# opentx.net
KiCad netlist of a schematic drawn in EAGLE
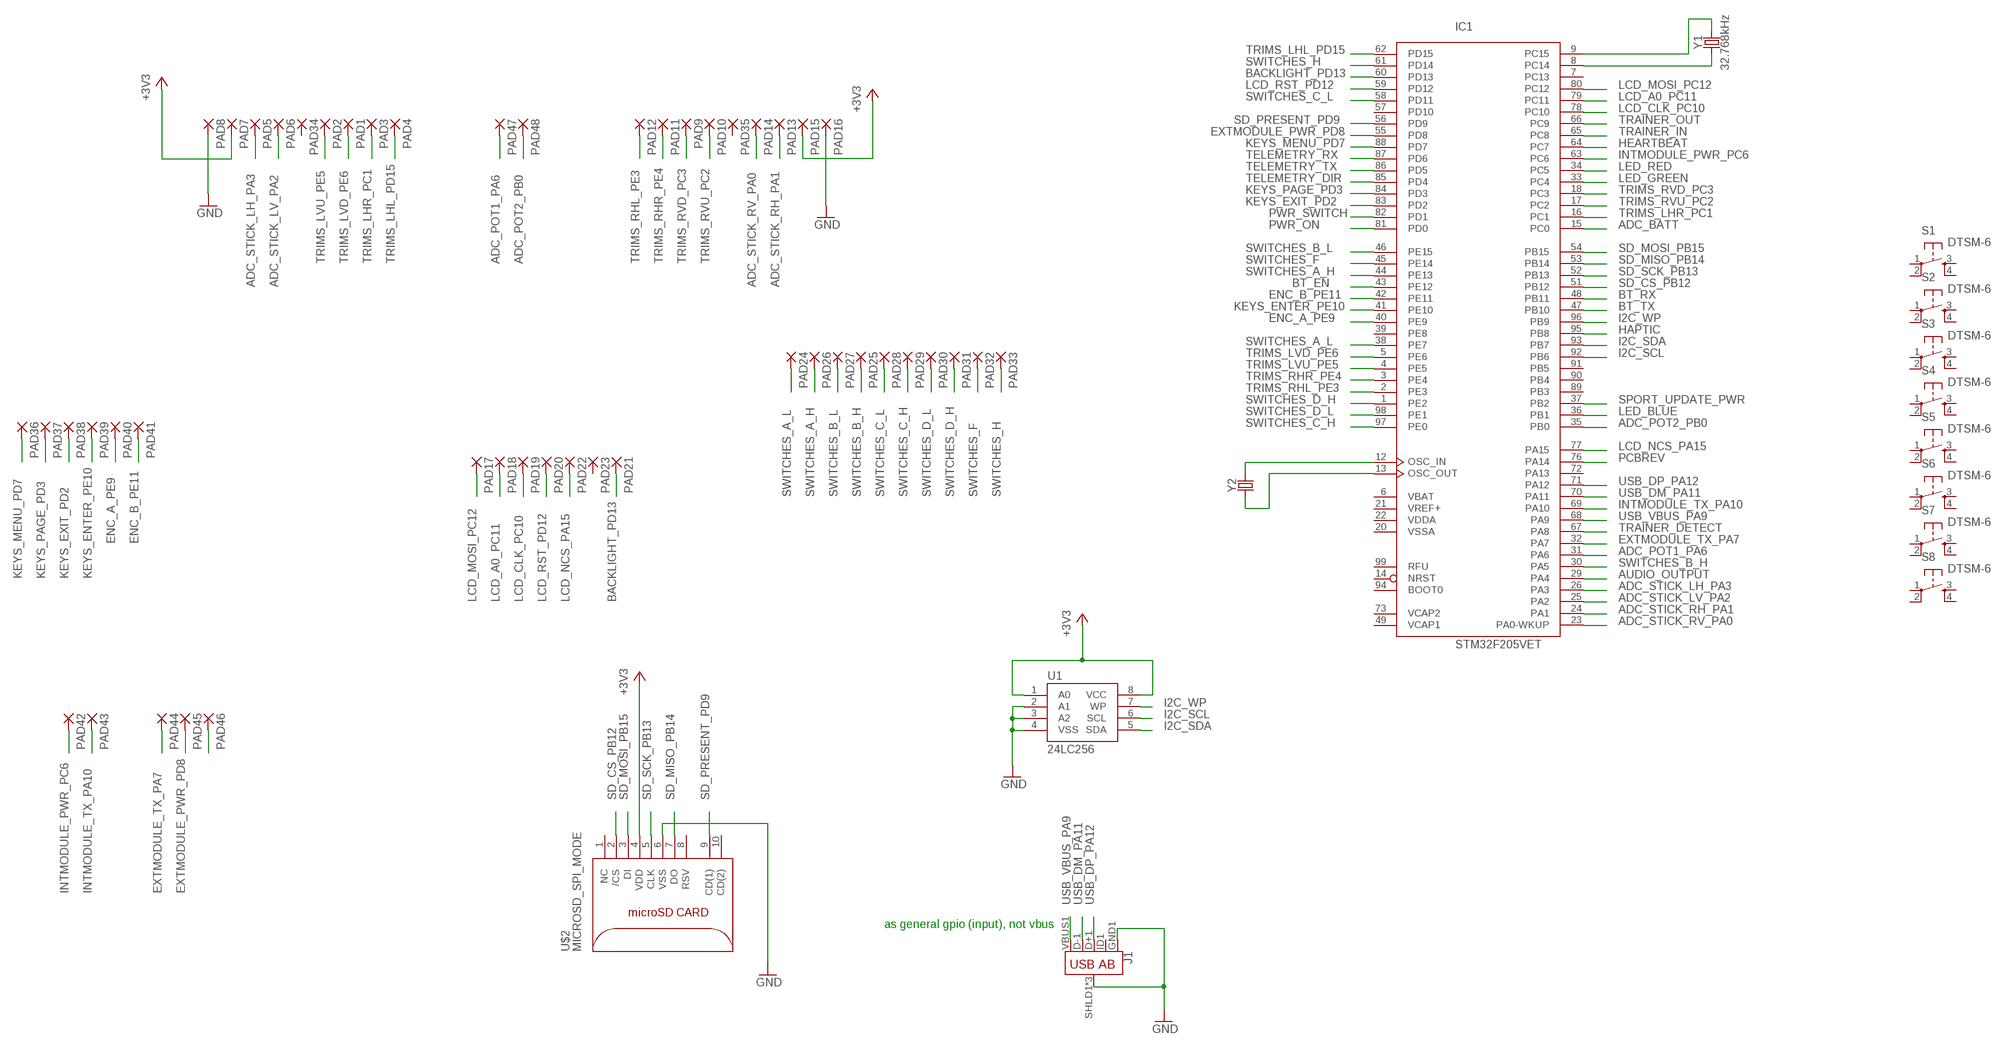
[diagram p0: schematic, sheet 1]

(export (version "E")
  (design (tool "Eeschema 10.0.6"))
  (components
    (comp (ref "IC1")
      (value "STM32F205VET")
      (footprint "eagle-import:LQFP100")
      (libsource (lib "eagle-import") (part "STM32F205VTE"))
    )
    (comp (ref "J1")
      (value "USB_AB_SMT")
      (footprint "eagle-import:USB-AB-MICRO-SMD")
      (libsource (lib "eagle-import") (part "USB_AB_SMT"))
    )
    (comp (ref "PAD1")
      (value "SMD2")
      (footprint "eagle-import:SMD1,27-2,54")
      (libsource (lib "eagle-import") (part "SMD2"))
    )
    (comp (ref "PAD2")
      (value "SMD2")
      (footprint "eagle-import:SMD1,27-2,54")
      (libsource (lib "eagle-import") (part "SMD2"))
    )
    (comp (ref "PAD3")
      (value "SMD2")
      (footprint "eagle-import:SMD1,27-2,54")
      (libsource (lib "eagle-import") (part "SMD2"))
    )
    (comp (ref "PAD4")
      (value "SMD2")
      (footprint "eagle-import:SMD1,27-2,54")
      (libsource (lib "eagle-import") (part "SMD2"))
    )
    (comp (ref "PAD5")
      (value "SMD2")
      (footprint "eagle-import:SMD1,27-2,54")
      (libsource (lib "eagle-import") (part "SMD2"))
    )
    (comp (ref "PAD6")
      (value "SMD2")
      (footprint "eagle-import:SMD1,27-2,54")
      (libsource (lib "eagle-import") (part "SMD2"))
    )
    (comp (ref "PAD7")
      (value "SMD2")
      (footprint "eagle-import:SMD1,27-2,54")
      (libsource (lib "eagle-import") (part "SMD2"))
    )
    (comp (ref "PAD8")
      (value "SMD2")
      (footprint "eagle-import:SMD1,27-2,54")
      (libsource (lib "eagle-import") (part "SMD2"))
    )
    (comp (ref "PAD9")
      (value "SMD2")
      (footprint "eagle-import:SMD1,27-2,54")
      (libsource (lib "eagle-import") (part "SMD2"))
    )
    (comp (ref "PAD10")
      (value "SMD2")
      (footprint "eagle-import:SMD1,27-2,54")
      (libsource (lib "eagle-import") (part "SMD2"))
    )
    (comp (ref "PAD11")
      (value "SMD2")
      (footprint "eagle-import:SMD1,27-2,54")
      (libsource (lib "eagle-import") (part "SMD2"))
    )
    (comp (ref "PAD12")
      (value "SMD2")
      (footprint "eagle-import:SMD1,27-2,54")
      (libsource (lib "eagle-import") (part "SMD2"))
    )
    (comp (ref "PAD13")
      (value "SMD2")
      (footprint "eagle-import:SMD1,27-2,54")
      (fields (field (name "SPICEPREFIX") "X"))
      (libsource (lib "eagle-import") (part "SMD2"))
    )
    (comp (ref "PAD14")
      (value "SMD2")
      (footprint "eagle-import:SMD1,27-2,54")
      (libsource (lib "eagle-import") (part "SMD2"))
    )
    (comp (ref "PAD15")
      (value "SMD2")
      (footprint "eagle-import:SMD1,27-2,54")
      (libsource (lib "eagle-import") (part "SMD2"))
    )
    (comp (ref "PAD16")
      (value "SMD2")
      (footprint "eagle-import:SMD1,27-2,54")
      (libsource (lib "eagle-import") (part "SMD2"))
    )
    (comp (ref "PAD17")
      (value "SMD2")
      (footprint "eagle-import:SMD1,27-2,54")
      (libsource (lib "eagle-import") (part "SMD2"))
    )
    (comp (ref "PAD18")
      (value "SMD2")
      (footprint "eagle-import:SMD1,27-2,54")
      (libsource (lib "eagle-import") (part "SMD2"))
    )
    (comp (ref "PAD19")
      (value "SMD2")
      (footprint "eagle-import:SMD1,27-2,54")
      (libsource (lib "eagle-import") (part "SMD2"))
    )
    (comp (ref "PAD20")
      (value "SMD2")
      (footprint "eagle-import:SMD1,27-2,54")
      (libsource (lib "eagle-import") (part "SMD2"))
    )
    (comp (ref "PAD21")
      (value "SMD2")
      (footprint "eagle-import:SMD1,27-2,54")
      (libsource (lib "eagle-import") (part "SMD2"))
    )
    (comp (ref "PAD22")
      (value "SMD2")
      (footprint "eagle-import:SMD1,27-2,54")
      (libsource (lib "eagle-import") (part "SMD2"))
    )
    (comp (ref "PAD23")
      (value "SMD2")
      (footprint "eagle-import:SMD1,27-2,54")
      (libsource (lib "eagle-import") (part "SMD2"))
    )
    (comp (ref "PAD24")
      (value "SMD2")
      (footprint "eagle-import:SMD1,27-2,54")
      (libsource (lib "eagle-import") (part "SMD2"))
    )
    (comp (ref "PAD25")
      (value "SMD2")
      (footprint "eagle-import:SMD1,27-2,54")
      (libsource (lib "eagle-import") (part "SMD2"))
    )
    (comp (ref "PAD26")
      (value "SMD2")
      (footprint "eagle-import:SMD1,27-2,54")
      (libsource (lib "eagle-import") (part "SMD2"))
    )
    (comp (ref "PAD27")
      (value "SMD2")
      (footprint "eagle-import:SMD1,27-2,54")
      (libsource (lib "eagle-import") (part "SMD2"))
    )
    (comp (ref "PAD28")
      (value "SMD2")
      (footprint "eagle-import:SMD1,27-2,54")
      (libsource (lib "eagle-import") (part "SMD2"))
    )
    (comp (ref "PAD29")
      (value "SMD2")
      (footprint "eagle-import:SMD1,27-2,54")
      (libsource (lib "eagle-import") (part "SMD2"))
    )
    (comp (ref "PAD30")
      (value "SMD2")
      (footprint "eagle-import:SMD1,27-2,54")
      (libsource (lib "eagle-import") (part "SMD2"))
    )
    (comp (ref "PAD31")
      (value "SMD2")
      (footprint "eagle-import:SMD1,27-2,54")
      (libsource (lib "eagle-import") (part "SMD2"))
    )
    (comp (ref "PAD32")
      (value "SMD2")
      (footprint "eagle-import:SMD1,27-2,54")
      (libsource (lib "eagle-import") (part "SMD2"))
    )
    (comp (ref "PAD33")
      (value "SMD2")
      (footprint "eagle-import:SMD1,27-2,54")
      (libsource (lib "eagle-import") (part "SMD2"))
    )
    (comp (ref "PAD34")
      (value "SMD2")
      (footprint "eagle-import:SMD1,27-2,54")
      (libsource (lib "eagle-import") (part "SMD2"))
    )
    (comp (ref "PAD35")
      (value "SMD2")
      (footprint "eagle-import:SMD1,27-2,54")
      (libsource (lib "eagle-import") (part "SMD2"))
    )
    (comp (ref "PAD36")
      (value "SMD2")
      (footprint "eagle-import:SMD1,27-2,54")
      (libsource (lib "eagle-import") (part "SMD2"))
    )
    (comp (ref "PAD37")
      (value "SMD2")
      (footprint "eagle-import:SMD1,27-2,54")
      (libsource (lib "eagle-import") (part "SMD2"))
    )
    (comp (ref "PAD38")
      (value "SMD2")
      (footprint "eagle-import:SMD1,27-2,54")
      (libsource (lib "eagle-import") (part "SMD2"))
    )
    (comp (ref "PAD39")
      (value "SMD2")
      (footprint "eagle-import:SMD1,27-2,54")
      (libsource (lib "eagle-import") (part "SMD2"))
    )
    (comp (ref "PAD40")
      (value "SMD2")
      (footprint "eagle-import:SMD1,27-2,54")
      (libsource (lib "eagle-import") (part "SMD2"))
    )
    (comp (ref "PAD41")
      (value "SMD2")
      (footprint "eagle-import:SMD1,27-2,54")
      (libsource (lib "eagle-import") (part "SMD2"))
    )
    (comp (ref "PAD42")
      (value "SMD2")
      (footprint "eagle-import:SMD1,27-2,54")
      (libsource (lib "eagle-import") (part "SMD2"))
    )
    (comp (ref "PAD43")
      (value "SMD2")
      (footprint "eagle-import:SMD1,27-2,54")
      (libsource (lib "eagle-import") (part "SMD2"))
    )
    (comp (ref "PAD44")
      (value "SMD2")
      (footprint "eagle-import:SMD1,27-2,54")
      (libsource (lib "eagle-import") (part "SMD2"))
    )
    (comp (ref "PAD45")
      (value "SMD2")
      (footprint "eagle-import:SMD1,27-2,54")
      (libsource (lib "eagle-import") (part "SMD2"))
    )
    (comp (ref "PAD46")
      (value "SMD2")
      (footprint "eagle-import:SMD1,27-2,54")
      (libsource (lib "eagle-import") (part "SMD2"))
    )
    (comp (ref "PAD47")
      (value "SMD2")
      (footprint "eagle-import:SMD1,27-2,54")
      (libsource (lib "eagle-import") (part "SMD2"))
    )
    (comp (ref "PAD48")
      (value "SMD2")
      (footprint "eagle-import:SMD1,27-2,54")
      (libsource (lib "eagle-import") (part "SMD2"))
    )
    (comp (ref "S1")
      (value "DTSM-6")
      (footprint "eagle-import:DTSM-6")
      (libsource (lib "eagle-import") (part "DTSM-6"))
    )
    (comp (ref "S2")
      (value "DTSM-6")
      (footprint "eagle-import:DTSM-6")
      (libsource (lib "eagle-import") (part "DTSM-6"))
    )
    (comp (ref "S3")
      (value "DTSM-6")
      (footprint "eagle-import:DTSM-6")
      (libsource (lib "eagle-import") (part "DTSM-6"))
    )
    (comp (ref "S4")
      (value "DTSM-6")
      (footprint "eagle-import:DTSM-6")
      (libsource (lib "eagle-import") (part "DTSM-6"))
    )
    (comp (ref "S5")
      (value "DTSM-6")
      (footprint "eagle-import:DTSM-6")
      (libsource (lib "eagle-import") (part "DTSM-6"))
    )
    (comp (ref "S6")
      (value "DTSM-6")
      (footprint "eagle-import:DTSM-6")
      (libsource (lib "eagle-import") (part "DTSM-6"))
    )
    (comp (ref "S7")
      (value "DTSM-6")
      (footprint "eagle-import:DTSM-6")
      (libsource (lib "eagle-import") (part "DTSM-6"))
    )
    (comp (ref "S8")
      (value "DTSM-6")
      (footprint "eagle-import:DTSM-6")
      (libsource (lib "eagle-import") (part "DTSM-6"))
    )
    (comp (ref "U$2")
      (value "MICROSD_SPI_MODE")
      (footprint "eagle-import:MICRO_SD_CONNECTOR")
      (libsource (lib "eagle-import") (part "MICROSD_SPI_MODE"))
    )
    (comp (ref "U1")
      (value "24LC256")
      (footprint "eagle-import:SO08")
      (libsource (lib "eagle-import") (part "EEPROM-I2CSMD"))
    )
    (comp (ref "Y1")
      (value "32.768kHz")
      (footprint "eagle-import:CRYSTAL-SMD-2X6-CYL")
      (libsource (lib "eagle-import") (part "CRYSTAL-32.768KHZSMD-2X6"))
    )
    (comp (ref "Y2")
      (value "CRYSTALSMD-HC49UP")
      (footprint "eagle-import:HC49UP")
      (libsource (lib "eagle-import") (part "CRYSTALSMD-HC49UP"))
    )
  )
  (nets
    (net (code "1") (name "+3V3") (class "Default")
      (node (ref "PAD15") (pin "1") (pinfunction "P_1") (pintype "passive"))
      (node (ref "PAD7") (pin "1") (pinfunction "P_1") (pintype "passive"))
      (node (ref "U$2") (pin "4") (pinfunction "VDD_4") (pintype "bidirectional"))
      (node (ref "U1") (pin "1") (pinfunction "A0_1") (pintype "bidirectional"))
      (node (ref "U1") (pin "8") (pinfunction "VCC_8") (pintype "power_in"))
    )
    (net (code "2") (name "/ADC_BATT") (class "Default")
      (node (ref "IC1") (pin "15") (pinfunction "PC0_15") (pintype "bidirectional"))
    )
    (net (code "3") (name "/ADC_POT1_PA6") (class "Default")
      (node (ref "IC1") (pin "31") (pinfunction "PA6_31") (pintype "bidirectional"))
      (node (ref "PAD47") (pin "1") (pinfunction "P_1") (pintype "passive"))
    )
    (net (code "4") (name "/ADC_POT2_PB0") (class "Default")
      (node (ref "IC1") (pin "35") (pinfunction "PB0_35") (pintype "bidirectional"))
      (node (ref "PAD48") (pin "1") (pinfunction "P_1") (pintype "passive"))
    )
    (net (code "5") (name "/ADC_STICK_LH_PA3") (class "Default")
      (node (ref "IC1") (pin "26") (pinfunction "PA3_26") (pintype "bidirectional"))
      (node (ref "PAD5") (pin "1") (pinfunction "P_1") (pintype "passive"))
    )
    (net (code "6") (name "/ADC_STICK_LV_PA2") (class "Default")
      (node (ref "IC1") (pin "25") (pinfunction "PA2_25") (pintype "bidirectional"))
      (node (ref "PAD6") (pin "1") (pinfunction "P_1") (pintype "passive"))
    )
    (net (code "7") (name "/ADC_STICK_RH_PA1") (class "Default")
      (node (ref "IC1") (pin "24") (pinfunction "PA1_24") (pintype "bidirectional"))
      (node (ref "PAD13") (pin "1") (pinfunction "P_1") (pintype "passive"))
    )
    (net (code "8") (name "/ADC_STICK_RV_PA0") (class "Default")
      (node (ref "IC1") (pin "23") (pinfunction "PA0-WKUP_23") (pintype "bidirectional"))
      (node (ref "PAD14") (pin "1") (pinfunction "P_1") (pintype "passive"))
    )
    (net (code "9") (name "/AUDIO_OUTPUT") (class "Default")
      (node (ref "IC1") (pin "29") (pinfunction "PA4_29") (pintype "bidirectional"))
    )
    (net (code "10") (name "/BACKLIGHT_PD13") (class "Default")
      (node (ref "IC1") (pin "60") (pinfunction "PD13_60") (pintype "bidirectional"))
      (node (ref "PAD21") (pin "1") (pinfunction "P_1") (pintype "passive"))
    )
    (net (code "11") (name "/BT_EN") (class "Default")
      (node (ref "IC1") (pin "43") (pinfunction "PE12_43") (pintype "bidirectional"))
    )
    (net (code "12") (name "/BT_RX") (class "Default")
      (node (ref "IC1") (pin "48") (pinfunction "PB11_48") (pintype "bidirectional"))
    )
    (net (code "13") (name "/BT_TX") (class "Default")
      (node (ref "IC1") (pin "47") (pinfunction "PB10_47") (pintype "bidirectional"))
    )
    (net (code "14") (name "/ENC_A_PE9") (class "Default")
      (node (ref "IC1") (pin "40") (pinfunction "PE9_40") (pintype "bidirectional"))
      (node (ref "PAD40") (pin "1") (pinfunction "P_1") (pintype "passive"))
    )
    (net (code "15") (name "/ENC_B_PE11") (class "Default")
      (node (ref "IC1") (pin "42") (pinfunction "PE11_42") (pintype "bidirectional"))
      (node (ref "PAD41") (pin "1") (pinfunction "P_1") (pintype "passive"))
    )
    (net (code "16") (name "/EXTMODULE_PWR_PD8") (class "Default")
      (node (ref "IC1") (pin "55") (pinfunction "PD8_55") (pintype "bidirectional"))
      (node (ref "PAD45") (pin "1") (pinfunction "P_1") (pintype "passive"))
    )
    (net (code "17") (name "/EXTMODULE_TX_PA7") (class "Default")
      (node (ref "IC1") (pin "32") (pinfunction "PA7_32") (pintype "bidirectional"))
      (node (ref "PAD44") (pin "1") (pinfunction "P_1") (pintype "passive"))
    )
    (net (code "18") (name "/HAPTIC") (class "Default")
      (node (ref "IC1") (pin "95") (pinfunction "PB8_95") (pintype "bidirectional"))
    )
    (net (code "19") (name "/HEARTBEAT") (class "Default")
      (node (ref "IC1") (pin "64") (pinfunction "PC7_64") (pintype "bidirectional"))
    )
    (net (code "20") (name "/I2C_SCL") (class "Default")
      (node (ref "IC1") (pin "92") (pinfunction "PB6_92") (pintype "bidirectional"))
      (node (ref "U1") (pin "6") (pinfunction "SCL_6") (pintype "bidirectional"))
    )
    (net (code "21") (name "/I2C_SDA") (class "Default")
      (node (ref "IC1") (pin "93") (pinfunction "PB7_93") (pintype "bidirectional"))
      (node (ref "U1") (pin "5") (pinfunction "SDA_5") (pintype "bidirectional"))
    )
    (net (code "22") (name "/I2C_WP") (class "Default")
      (node (ref "IC1") (pin "96") (pinfunction "PB9_96") (pintype "bidirectional"))
      (node (ref "U1") (pin "7") (pinfunction "WP_7") (pintype "bidirectional"))
    )
    (net (code "23") (name "/INTMODULE_PWR_PC6") (class "Default")
      (node (ref "IC1") (pin "63") (pinfunction "PC6_63") (pintype "bidirectional"))
      (node (ref "PAD42") (pin "1") (pinfunction "P_1") (pintype "passive"))
    )
    (net (code "24") (name "/INTMODULE_TX_PA10") (class "Default")
      (node (ref "IC1") (pin "69") (pinfunction "PA10_69") (pintype "bidirectional"))
      (node (ref "PAD43") (pin "1") (pinfunction "P_1") (pintype "passive"))
    )
    (net (code "25") (name "/KEYS_ENTER_PE10") (class "Default")
      (node (ref "IC1") (pin "41") (pinfunction "PE10_41") (pintype "bidirectional"))
      (node (ref "PAD39") (pin "1") (pinfunction "P_1") (pintype "passive"))
    )
    (net (code "26") (name "/KEYS_EXIT_PD2") (class "Default")
      (node (ref "IC1") (pin "83") (pinfunction "PD2_83") (pintype "bidirectional"))
      (node (ref "PAD38") (pin "1") (pinfunction "P_1") (pintype "passive"))
    )
    (net (code "27") (name "/KEYS_MENU_PD7") (class "Default")
      (node (ref "IC1") (pin "88") (pinfunction "PD7_88") (pintype "bidirectional"))
      (node (ref "PAD36") (pin "1") (pinfunction "P_1") (pintype "passive"))
    )
    (net (code "28") (name "/KEYS_PAGE_PD3") (class "Default")
      (node (ref "IC1") (pin "84") (pinfunction "PD3_84") (pintype "bidirectional"))
      (node (ref "PAD37") (pin "1") (pinfunction "P_1") (pintype "passive"))
    )
    (net (code "29") (name "/LCD_A0_PC11") (class "Default")
      (node (ref "IC1") (pin "79") (pinfunction "PC11_79") (pintype "bidirectional"))
      (node (ref "PAD18") (pin "1") (pinfunction "P_1") (pintype "passive"))
    )
    (net (code "30") (name "/LCD_CLK_PC10") (class "Default")
      (node (ref "IC1") (pin "78") (pinfunction "PC10_78") (pintype "bidirectional"))
      (node (ref "PAD19") (pin "1") (pinfunction "P_1") (pintype "passive"))
    )
    (net (code "31") (name "/LCD_MOSI_PC12") (class "Default")
      (node (ref "IC1") (pin "80") (pinfunction "PC12_80") (pintype "bidirectional"))
      (node (ref "PAD17") (pin "1") (pinfunction "P_1") (pintype "passive"))
    )
    (net (code "32") (name "/LCD_NCS_PA15") (class "Default")
      (node (ref "IC1") (pin "77") (pinfunction "PA15_77") (pintype "bidirectional"))
      (node (ref "PAD22") (pin "1") (pinfunction "P_1") (pintype "passive"))
    )
    (net (code "33") (name "/LCD_RST_PD12") (class "Default")
      (node (ref "IC1") (pin "59") (pinfunction "PD12_59") (pintype "bidirectional"))
      (node (ref "PAD20") (pin "1") (pinfunction "P_1") (pintype "passive"))
    )
    (net (code "34") (name "/LED_BLUE") (class "Default")
      (node (ref "IC1") (pin "36") (pinfunction "PB1_36") (pintype "bidirectional"))
    )
    (net (code "35") (name "/LED_GREEN") (class "Default")
      (node (ref "IC1") (pin "33") (pinfunction "PC4_33") (pintype "bidirectional"))
    )
    (net (code "36") (name "/LED_RED") (class "Default")
      (node (ref "IC1") (pin "34") (pinfunction "PC5_34") (pintype "bidirectional"))
    )
    (net (code "37") (name "/PCBREV") (class "Default")
      (node (ref "IC1") (pin "76") (pinfunction "PA14_76") (pintype "bidirectional"))
    )
    (net (code "38") (name "/PWR_ON") (class "Default")
      (node (ref "IC1") (pin "81") (pinfunction "PD0_81") (pintype "bidirectional"))
    )
    (net (code "39") (name "/PWR_SWITCH") (class "Default")
      (node (ref "IC1") (pin "82") (pinfunction "PD1_82") (pintype "bidirectional"))
    )
    (net (code "40") (name "/SD_CS_PB12") (class "Default")
      (node (ref "IC1") (pin "51") (pinfunction "PB12_51") (pintype "bidirectional"))
      (node (ref "U$2") (pin "2") (pinfunction "/CS_2") (pintype "bidirectional"))
    )
    (net (code "41") (name "/SD_MISO_PB14") (class "Default")
      (node (ref "IC1") (pin "53") (pinfunction "PB14_53") (pintype "bidirectional"))
      (node (ref "U$2") (pin "7") (pinfunction "DO_7") (pintype "bidirectional"))
    )
    (net (code "42") (name "/SD_MOSI_PB15") (class "Default")
      (node (ref "IC1") (pin "54") (pinfunction "PB15_54") (pintype "bidirectional"))
      (node (ref "U$2") (pin "3") (pinfunction "DI_3") (pintype "bidirectional"))
    )
    (net (code "43") (name "/SD_PRESENT_PD9") (class "Default")
      (node (ref "IC1") (pin "56") (pinfunction "PD9_56") (pintype "bidirectional"))
      (node (ref "U$2") (pin "9") (pinfunction "CD(1)_9") (pintype "bidirectional"))
    )
    (net (code "44") (name "/SD_SCK_PB13") (class "Default")
      (node (ref "IC1") (pin "52") (pinfunction "PB13_52") (pintype "bidirectional"))
      (node (ref "U$2") (pin "5") (pinfunction "CLK_5") (pintype "bidirectional"))
    )
    (net (code "45") (name "/SPORT_UPDATE_PWR") (class "Default")
      (node (ref "IC1") (pin "37") (pinfunction "PB2_37") (pintype "bidirectional"))
    )
    (net (code "46") (name "/SWITCHES_A_H") (class "Default")
      (node (ref "IC1") (pin "44") (pinfunction "PE13_44") (pintype "bidirectional"))
      (node (ref "PAD26") (pin "1") (pinfunction "P_1") (pintype "passive"))
    )
    (net (code "47") (name "/SWITCHES_A_L") (class "Default")
      (node (ref "IC1") (pin "38") (pinfunction "PE7_38") (pintype "bidirectional"))
      (node (ref "PAD24") (pin "1") (pinfunction "P_1") (pintype "passive"))
    )
    (net (code "48") (name "/SWITCHES_B_H") (class "Default")
      (node (ref "IC1") (pin "30") (pinfunction "PA5_30") (pintype "bidirectional"))
      (node (ref "PAD25") (pin "1") (pinfunction "P_1") (pintype "passive"))
    )
    (net (code "49") (name "/SWITCHES_B_L") (class "Default")
      (node (ref "IC1") (pin "46") (pinfunction "PE15_46") (pintype "bidirectional"))
      (node (ref "PAD27") (pin "1") (pinfunction "P_1") (pintype "passive"))
    )
    (net (code "50") (name "/SWITCHES_C_H") (class "Default")
      (node (ref "IC1") (pin "97") (pinfunction "PE0_97") (pintype "bidirectional"))
      (node (ref "PAD29") (pin "1") (pinfunction "P_1") (pintype "passive"))
    )
    (net (code "51") (name "/SWITCHES_C_L") (class "Default")
      (node (ref "IC1") (pin "58") (pinfunction "PD11_58") (pintype "bidirectional"))
      (node (ref "PAD28") (pin "1") (pinfunction "P_1") (pintype "passive"))
    )
    (net (code "52") (name "/SWITCHES_D_H") (class "Default")
      (node (ref "IC1") (pin "1") (pinfunction "PE2_1") (pintype "bidirectional"))
      (node (ref "PAD31") (pin "1") (pinfunction "P_1") (pintype "passive"))
    )
    (net (code "53") (name "/SWITCHES_D_L") (class "Default")
      (node (ref "IC1") (pin "98") (pinfunction "PE1_98") (pintype "bidirectional"))
      (node (ref "PAD30") (pin "1") (pinfunction "P_1") (pintype "passive"))
    )
    (net (code "54") (name "/SWITCHES_F") (class "Default")
      (node (ref "IC1") (pin "45") (pinfunction "PE14_45") (pintype "bidirectional"))
      (node (ref "PAD32") (pin "1") (pinfunction "P_1") (pintype "passive"))
    )
    (net (code "55") (name "/SWITCHES_H") (class "Default")
      (node (ref "IC1") (pin "61") (pinfunction "PD14_61") (pintype "bidirectional"))
      (node (ref "PAD33") (pin "1") (pinfunction "P_1") (pintype "passive"))
    )
    (net (code "56") (name "/TELEMETRY_DIR") (class "Default")
      (node (ref "IC1") (pin "85") (pinfunction "PD4_85") (pintype "bidirectional"))
    )
    (net (code "57") (name "/TELEMETRY_RX") (class "Default")
      (node (ref "IC1") (pin "87") (pinfunction "PD6_87") (pintype "bidirectional"))
    )
    (net (code "58") (name "/TELEMETRY_TX") (class "Default")
      (node (ref "IC1") (pin "86") (pinfunction "PD5_86") (pintype "bidirectional"))
    )
    (net (code "59") (name "/TRAINER_DETECT") (class "Default")
      (node (ref "IC1") (pin "67") (pinfunction "PA8_67") (pintype "bidirectional"))
    )
    (net (code "60") (name "/TRAINER_IN") (class "Default")
      (node (ref "IC1") (pin "65") (pinfunction "PC8_65") (pintype "bidirectional"))
    )
    (net (code "61") (name "/TRAINER_OUT") (class "Default")
      (node (ref "IC1") (pin "66") (pinfunction "PC9_66") (pintype "bidirectional"))
    )
    (net (code "62") (name "/TRIMS_LHL_PD15") (class "Default")
      (node (ref "IC1") (pin "62") (pinfunction "PD15_62") (pintype "bidirectional"))
      (node (ref "PAD4") (pin "1") (pinfunction "P_1") (pintype "passive"))
    )
    (net (code "63") (name "/TRIMS_LHR_PC1") (class "Default")
      (node (ref "IC1") (pin "16") (pinfunction "PC1_16") (pintype "bidirectional"))
      (node (ref "PAD3") (pin "1") (pinfunction "P_1") (pintype "passive"))
    )
    (net (code "64") (name "/TRIMS_LVD_PE6") (class "Default")
      (node (ref "IC1") (pin "5") (pinfunction "PE6_5") (pintype "bidirectional"))
      (node (ref "PAD1") (pin "1") (pinfunction "P_1") (pintype "passive"))
    )
    (net (code "65") (name "/TRIMS_LVU_PE5") (class "Default")
      (node (ref "IC1") (pin "4") (pinfunction "PE5_4") (pintype "bidirectional"))
      (node (ref "PAD2") (pin "1") (pinfunction "P_1") (pintype "passive"))
    )
    (net (code "66") (name "/TRIMS_RHL_PE3") (class "Default")
      (node (ref "IC1") (pin "2") (pinfunction "PE3_2") (pintype "bidirectional"))
      (node (ref "PAD12") (pin "1") (pinfunction "P_1") (pintype "passive"))
    )
    (net (code "67") (name "/TRIMS_RHR_PE4") (class "Default")
      (node (ref "IC1") (pin "3") (pinfunction "PE4_3") (pintype "bidirectional"))
      (node (ref "PAD11") (pin "1") (pinfunction "P_1") (pintype "passive"))
    )
    (net (code "68") (name "/TRIMS_RVD_PC3") (class "Default")
      (node (ref "IC1") (pin "18") (pinfunction "PC3_18") (pintype "bidirectional"))
      (node (ref "PAD9") (pin "1") (pinfunction "P_1") (pintype "passive"))
    )
    (net (code "69") (name "/TRIMS_RVU_PC2") (class "Default")
      (node (ref "IC1") (pin "17") (pinfunction "PC2_17") (pintype "bidirectional"))
      (node (ref "PAD10") (pin "1") (pinfunction "P_1") (pintype "passive"))
    )
    (net (code "70") (name "/USB_DM_PA11") (class "Default")
      (node (ref "IC1") (pin "70") (pinfunction "PA11_70") (pintype "bidirectional"))
      (node (ref "J1") (pin "D-1") (pinfunction "D-_D-1") (pintype "bidirectional"))
    )
    (net (code "71") (name "/USB_DP_PA12") (class "Default")
      (node (ref "IC1") (pin "71") (pinfunction "PA12_71") (pintype "bidirectional"))
      (node (ref "J1") (pin "D+1") (pinfunction "D+_D+1") (pintype "bidirectional"))
    )
    (net (code "72") (name "/USB_VBUS_PA9") (class "Default")
      (node (ref "IC1") (pin "68") (pinfunction "PA9_68") (pintype "bidirectional"))
      (node (ref "J1") (pin "VBUS1") (pinfunction "VBUS_VBUS1") (pintype "power_in"))
    )
    (net (code "73") (name "/VBAT") (class "Default")
      (node (ref "IC1") (pin "6") (pinfunction "VBAT_6") (pintype "power_in"))
    )
    (net (code "74") (name "/VCAP1") (class "Default")
      (node (ref "IC1") (pin "49") (pinfunction "VCAP1_49") (pintype "power_in"))
    )
    (net (code "75") (name "/VCAP2") (class "Default")
      (node (ref "IC1") (pin "73") (pinfunction "VCAP2_73") (pintype "power_in"))
    )
    (net (code "76") (name "/VDDA") (class "Default")
      (node (ref "IC1") (pin "22") (pinfunction "VDDA_22") (pintype "power_in"))
    )
    (net (code "77") (name "/VREF+") (class "Default")
      (node (ref "IC1") (pin "21") (pinfunction "VREF+_21") (pintype "power_in"))
    )
    (net (code "78") (name "/VSSA") (class "Default")
      (node (ref "IC1") (pin "20") (pinfunction "VSSA_20") (pintype "power_in"))
    )
    (net (code "79") (name "GND") (class "Default")
      (node (ref "J1") (pin "GND1") (pinfunction "GND_GND1") (pintype "power_in"))
      (node (ref "J1") (pin "SHLD1") (pinfunction "SHIELD_SHLD1") (pintype "bidirectional"))
      (node (ref "J1") (pin "SHLD2") (pinfunction "SHIELD_SHLD2") (pintype "bidirectional"))
      (node (ref "J1") (pin "SHLD3") (pinfunction "SHIELD_SHLD3") (pintype "bidirectional"))
      (node (ref "PAD16") (pin "1") (pinfunction "P_1") (pintype "passive"))
      (node (ref "PAD8") (pin "1") (pinfunction "P_1") (pintype "passive"))
      (node (ref "U$2") (pin "6") (pinfunction "VSS_6") (pintype "bidirectional"))
      (node (ref "U1") (pin "2") (pinfunction "A1_2") (pintype "bidirectional"))
      (node (ref "U1") (pin "3") (pinfunction "A2_3") (pintype "bidirectional"))
      (node (ref "U1") (pin "4") (pinfunction "VSS_4") (pintype "power_in"))
    )
    (net (code "80") (name "Net-(IC1A-OSC_IN)") (class "Default")
      (node (ref "IC1") (pin "12") (pinfunction "OSC_IN_12") (pintype "bidirectional"))
      (node (ref "Y2") (pin "2") (pinfunction "2_2") (pintype "passive"))
    )
    (net (code "81") (name "Net-(IC1A-OSC_OUT)") (class "Default")
      (node (ref "IC1") (pin "13") (pinfunction "OSC_OUT_13") (pintype "bidirectional"))
      (node (ref "Y2") (pin "1") (pinfunction "1_1") (pintype "passive"))
    )
    (net (code "82") (name "Net-(IC1A-PC14)") (class "Default")
      (node (ref "IC1") (pin "8") (pinfunction "PC14_8") (pintype "bidirectional"))
      (node (ref "Y1") (pin "X1") (pinfunction "1_X1") (pintype "passive"))
    )
    (net (code "83") (name "Net-(IC1A-PC15)") (class "Default")
      (node (ref "IC1") (pin "9") (pinfunction "PC15_9") (pintype "bidirectional"))
      (node (ref "Y1") (pin "X2") (pinfunction "2_X2") (pintype "passive"))
    )
    (net (code "84") (name "unconnected-(IC1A-BOOT0-Pad94)") (class "Default")
      (node (ref "IC1") (pin "94") (pinfunction "BOOT0_94") (pintype "input"))
    )
    (net (code "85") (name "unconnected-(IC1A-NRST-Pad14)") (class "Default")
      (node (ref "IC1") (pin "14") (pinfunction "NRST_14") (pintype "bidirectional"))
    )
    (net (code "86") (name "unconnected-(IC1A-PA13-Pad72)") (class "Default")
      (node (ref "IC1") (pin "72") (pinfunction "PA13_72") (pintype "bidirectional"))
    )
    (net (code "87") (name "unconnected-(IC1A-PB3-Pad89)") (class "Default")
      (node (ref "IC1") (pin "89") (pinfunction "PB3_89") (pintype "bidirectional"))
    )
    (net (code "88") (name "unconnected-(IC1A-PB4-Pad90)") (class "Default")
      (node (ref "IC1") (pin "90") (pinfunction "PB4_90") (pintype "bidirectional"))
    )
    (net (code "89") (name "unconnected-(IC1A-PB5-Pad91)") (class "Default")
      (node (ref "IC1") (pin "91") (pinfunction "PB5_91") (pintype "bidirectional"))
    )
    (net (code "90") (name "unconnected-(IC1A-PC13-Pad7)") (class "Default")
      (node (ref "IC1") (pin "7") (pinfunction "PC13_7") (pintype "bidirectional"))
    )
    (net (code "91") (name "unconnected-(IC1A-PD10-Pad57)") (class "Default")
      (node (ref "IC1") (pin "57") (pinfunction "PD10_57") (pintype "bidirectional"))
    )
    (net (code "92") (name "unconnected-(IC1A-PE8-Pad39)") (class "Default")
      (node (ref "IC1") (pin "39") (pinfunction "PE8_39") (pintype "bidirectional"))
    )
    (net (code "93") (name "unconnected-(IC1A-RFU-Pad99)") (class "Default")
      (node (ref "IC1") (pin "99") (pinfunction "RFU_99") (pintype "input"))
    )
    (net (code "94") (name "unconnected-(J1-USBID-PadID1)") (class "Default")
      (node (ref "J1") (pin "ID1") (pinfunction "USBID_ID1") (pintype "bidirectional"))
    )
    (net (code "95") (name "unconnected-(PAD23-P-Pad1)") (class "Default")
      (node (ref "PAD23") (pin "1") (pinfunction "P_1") (pintype "passive"))
    )
    (net (code "96") (name "unconnected-(PAD34-P-Pad1)") (class "Default")
      (node (ref "PAD34") (pin "1") (pinfunction "P_1") (pintype "passive"))
    )
    (net (code "97") (name "unconnected-(PAD35-P-Pad1)") (class "Default")
      (node (ref "PAD35") (pin "1") (pinfunction "P_1") (pintype "passive"))
    )
    (net (code "98") (name "unconnected-(PAD46-P-Pad1)") (class "Default")
      (node (ref "PAD46") (pin "1") (pinfunction "P_1") (pintype "passive"))
    )
    (net (code "99") (name "unconnected-(S1-Pad1)") (class "Default")
      (node (ref "S1") (pin "1") (pinfunction "1_1") (pintype "passive"))
    )
    (net (code "100") (name "unconnected-(S1-Pad2)") (class "Default")
      (node (ref "S1") (pin "2") (pinfunction "2_2") (pintype "passive"))
    )
    (net (code "101") (name "unconnected-(S1-Pad3)") (class "Default")
      (node (ref "S1") (pin "3") (pinfunction "3_3") (pintype "passive"))
    )
    (net (code "102") (name "unconnected-(S1-Pad4)") (class "Default")
      (node (ref "S1") (pin "4") (pinfunction "4_4") (pintype "passive"))
    )
    (net (code "103") (name "unconnected-(S2-Pad1)") (class "Default")
      (node (ref "S2") (pin "1") (pinfunction "1_1") (pintype "passive"))
    )
    (net (code "104") (name "unconnected-(S2-Pad2)") (class "Default")
      (node (ref "S2") (pin "2") (pinfunction "2_2") (pintype "passive"))
    )
    (net (code "105") (name "unconnected-(S2-Pad3)") (class "Default")
      (node (ref "S2") (pin "3") (pinfunction "3_3") (pintype "passive"))
    )
    (net (code "106") (name "unconnected-(S2-Pad4)") (class "Default")
      (node (ref "S2") (pin "4") (pinfunction "4_4") (pintype "passive"))
    )
    (net (code "107") (name "unconnected-(S3-Pad1)") (class "Default")
      (node (ref "S3") (pin "1") (pinfunction "1_1") (pintype "passive"))
    )
    (net (code "108") (name "unconnected-(S3-Pad2)") (class "Default")
      (node (ref "S3") (pin "2") (pinfunction "2_2") (pintype "passive"))
    )
    (net (code "109") (name "unconnected-(S3-Pad3)") (class "Default")
      (node (ref "S3") (pin "3") (pinfunction "3_3") (pintype "passive"))
    )
    (net (code "110") (name "unconnected-(S3-Pad4)") (class "Default")
      (node (ref "S3") (pin "4") (pinfunction "4_4") (pintype "passive"))
    )
    (net (code "111") (name "unconnected-(S4-Pad1)") (class "Default")
      (node (ref "S4") (pin "1") (pinfunction "1_1") (pintype "passive"))
    )
    (net (code "112") (name "unconnected-(S4-Pad2)") (class "Default")
      (node (ref "S4") (pin "2") (pinfunction "2_2") (pintype "passive"))
    )
    (net (code "113") (name "unconnected-(S4-Pad3)") (class "Default")
      (node (ref "S4") (pin "3") (pinfunction "3_3") (pintype "passive"))
    )
    (net (code "114") (name "unconnected-(S4-Pad4)") (class "Default")
      (node (ref "S4") (pin "4") (pinfunction "4_4") (pintype "passive"))
    )
    (net (code "115") (name "unconnected-(S5-Pad1)") (class "Default")
      (node (ref "S5") (pin "1") (pinfunction "1_1") (pintype "passive"))
    )
    (net (code "116") (name "unconnected-(S5-Pad2)") (class "Default")
      (node (ref "S5") (pin "2") (pinfunction "2_2") (pintype "passive"))
    )
    (net (code "117") (name "unconnected-(S5-Pad3)") (class "Default")
      (node (ref "S5") (pin "3") (pinfunction "3_3") (pintype "passive"))
    )
    (net (code "118") (name "unconnected-(S5-Pad4)") (class "Default")
      (node (ref "S5") (pin "4") (pinfunction "4_4") (pintype "passive"))
    )
    (net (code "119") (name "unconnected-(S6-Pad1)") (class "Default")
      (node (ref "S6") (pin "1") (pinfunction "1_1") (pintype "passive"))
    )
    (net (code "120") (name "unconnected-(S6-Pad2)") (class "Default")
      (node (ref "S6") (pin "2") (pinfunction "2_2") (pintype "passive"))
    )
    (net (code "121") (name "unconnected-(S6-Pad3)") (class "Default")
      (node (ref "S6") (pin "3") (pinfunction "3_3") (pintype "passive"))
    )
    (net (code "122") (name "unconnected-(S6-Pad4)") (class "Default")
      (node (ref "S6") (pin "4") (pinfunction "4_4") (pintype "passive"))
    )
    (net (code "123") (name "unconnected-(S7-Pad1)") (class "Default")
      (node (ref "S7") (pin "1") (pinfunction "1_1") (pintype "passive"))
    )
    (net (code "124") (name "unconnected-(S7-Pad2)") (class "Default")
      (node (ref "S7") (pin "2") (pinfunction "2_2") (pintype "passive"))
    )
    (net (code "125") (name "unconnected-(S7-Pad3)") (class "Default")
      (node (ref "S7") (pin "3") (pinfunction "3_3") (pintype "passive"))
    )
    (net (code "126") (name "unconnected-(S7-Pad4)") (class "Default")
      (node (ref "S7") (pin "4") (pinfunction "4_4") (pintype "passive"))
    )
    (net (code "127") (name "unconnected-(S8-Pad1)") (class "Default")
      (node (ref "S8") (pin "1") (pinfunction "1_1") (pintype "passive"))
    )
    (net (code "128") (name "unconnected-(S8-Pad2)") (class "Default")
      (node (ref "S8") (pin "2") (pinfunction "2_2") (pintype "passive"))
    )
    (net (code "129") (name "unconnected-(S8-Pad3)") (class "Default")
      (node (ref "S8") (pin "3") (pinfunction "3_3") (pintype "passive"))
    )
    (net (code "130") (name "unconnected-(S8-Pad4)") (class "Default")
      (node (ref "S8") (pin "4") (pinfunction "4_4") (pintype "passive"))
    )
    (net (code "131") (name "unconnected-(U$2-CD(2)-Pad10)") (class "Default")
      (node (ref "U$2") (pin "10") (pinfunction "CD(2)_10") (pintype "bidirectional"))
    )
    (net (code "132") (name "unconnected-(U$2-NC-Pad1)") (class "Default")
      (node (ref "U$2") (pin "1") (pinfunction "NC_1") (pintype "bidirectional"))
    )
    (net (code "133") (name "unconnected-(U$2-RSV-Pad8)") (class "Default")
      (node (ref "U$2") (pin "8") (pinfunction "RSV_8") (pintype "bidirectional"))
    )
  )
)
